# 07_AD9363.net
KiCad netlist of a schematic drawn in Altium Designer
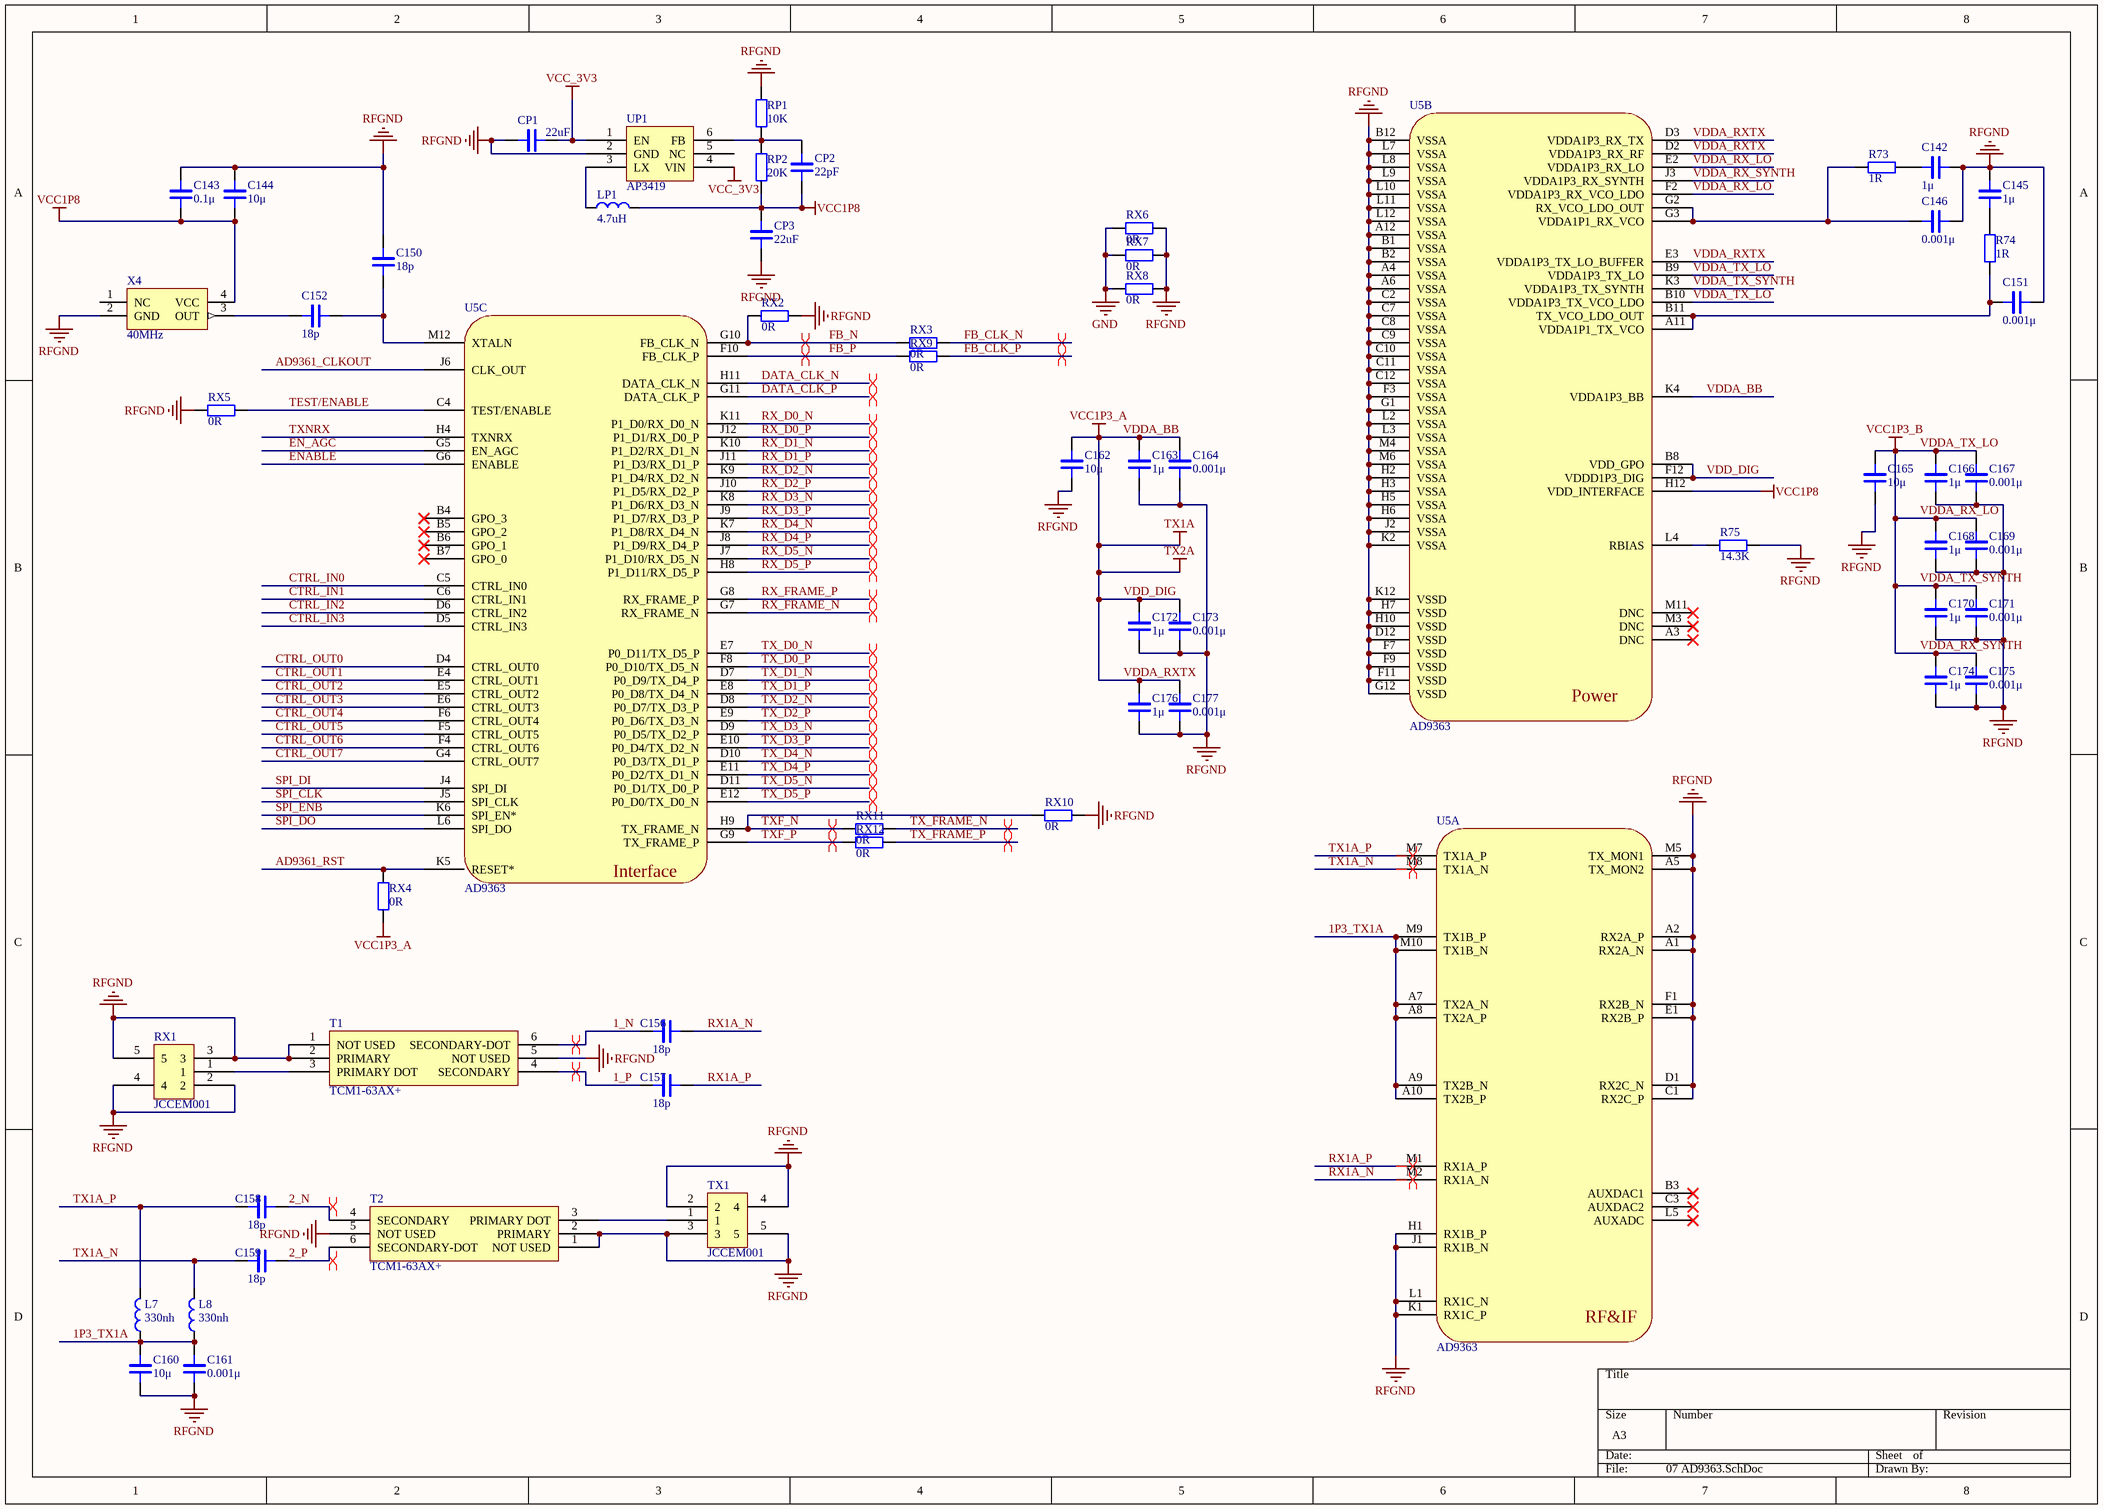
[diagram p0: 07 AD9363.SchDoc]

(export (version "E")
  (design (tool "Eeschema 10.0.6"))
  (components
    (comp (ref "C142")
      (value "1μ")
      (footprint "LC-0402_C")
      (description "Capacitor")
      (libsource (lib "DDR3_xc7z010-clg400") (part "CAP_2"))
    )
    (comp (ref "C143")
      (value "0.1μ")
      (footprint "LC-0402_C")
      (description "Capacitor")
      (libsource (lib "DDR3_xc7z010-clg400") (part "CAP_2"))
    )
    (comp (ref "C144")
      (value "10μ")
      (footprint "LC-0402_C")
      (description "Capacitor")
      (libsource (lib "DDR3_xc7z010-clg400") (part "CAP_2"))
    )
    (comp (ref "C145")
      (value "1μ")
      (footprint "LC-0402_C")
      (description "Capacitor")
      (libsource (lib "DDR3_xc7z010-clg400") (part "CAP_1"))
    )
    (comp (ref "C146")
      (value "0.001μ")
      (footprint "LC-0402_C")
      (description "Capacitor")
      (libsource (lib "DDR3_xc7z010-clg400") (part "CAP_1"))
    )
    (comp (ref "C150")
      (value "18p")
      (footprint "LC-0402_C")
      (description "Capacitor")
      (libsource (lib "DDR3_xc7z010-clg400") (part "CAP_1"))
    )
    (comp (ref "C151")
      (value "0.001μ")
      (footprint "LC-0402_C")
      (description "Capacitor")
      (libsource (lib "DDR3_xc7z010-clg400") (part "CAP_1"))
    )
    (comp (ref "C152")
      (value "18p")
      (footprint "LC-0402_C")
      (description "Capacitor")
      (libsource (lib "DDR3_xc7z010-clg400") (part "CAP_1"))
    )
    (comp (ref "C156")
      (value "18p")
      (footprint "LC-0402_C")
      (description "Capacitor")
      (libsource (lib "DDR3_xc7z010-clg400") (part "CAP_1"))
    )
    (comp (ref "C157")
      (value "18p")
      (footprint "LC-0402_C")
      (description "Capacitor")
      (libsource (lib "DDR3_xc7z010-clg400") (part "CAP_1"))
    )
    (comp (ref "C158")
      (value "18p")
      (footprint "LC-0402_C")
      (description "Capacitor")
      (libsource (lib "DDR3_xc7z010-clg400") (part "CAP_1"))
    )
    (comp (ref "C159")
      (value "18p")
      (footprint "LC-0402_C")
      (description "Capacitor")
      (libsource (lib "DDR3_xc7z010-clg400") (part "CAP_1"))
    )
    (comp (ref "C160")
      (value "10μ")
      (footprint "LC-0402_C")
      (description "Capacitor")
      (libsource (lib "DDR3_xc7z010-clg400") (part "CAP_2"))
    )
    (comp (ref "C161")
      (value "0.001μ")
      (footprint "LC-0402_C")
      (description "Capacitor")
      (libsource (lib "DDR3_xc7z010-clg400") (part "CAP_2"))
    )
    (comp (ref "C162")
      (value "10μ")
      (footprint "LC-0402_C")
      (description "Capacitor")
      (libsource (lib "DDR3_xc7z010-clg400") (part "CAP_1"))
    )
    (comp (ref "C163")
      (value "1μ")
      (footprint "LC-0402_C")
      (description "Capacitor")
      (libsource (lib "DDR3_xc7z010-clg400") (part "CAP_1"))
    )
    (comp (ref "C164")
      (value "0.001μ")
      (footprint "LC-0402_C")
      (description "Capacitor")
      (libsource (lib "DDR3_xc7z010-clg400") (part "CAP_1"))
    )
    (comp (ref "C165")
      (value "10μ")
      (footprint "LC-0402_C")
      (description "Capacitor")
      (libsource (lib "DDR3_xc7z010-clg400") (part "CAP_1"))
    )
    (comp (ref "C166")
      (value "1μ")
      (footprint "LC-0402_C")
      (description "Capacitor")
      (libsource (lib "DDR3_xc7z010-clg400") (part "CAP_1"))
    )
    (comp (ref "C167")
      (value "0.001μ")
      (footprint "LC-0402_C")
      (description "Capacitor")
      (libsource (lib "DDR3_xc7z010-clg400") (part "CAP_1"))
    )
    (comp (ref "C168")
      (value "1μ")
      (footprint "LC-0402_C")
      (description "Capacitor")
      (libsource (lib "DDR3_xc7z010-clg400") (part "CAP_1"))
    )
    (comp (ref "C169")
      (value "0.001μ")
      (footprint "LC-0402_C")
      (description "Capacitor")
      (libsource (lib "DDR3_xc7z010-clg400") (part "CAP_1"))
    )
    (comp (ref "C170")
      (value "1μ")
      (footprint "LC-0402_C")
      (description "Capacitor")
      (libsource (lib "DDR3_xc7z010-clg400") (part "CAP_1"))
    )
    (comp (ref "C171")
      (value "0.001μ")
      (footprint "LC-0402_C")
      (description "Capacitor")
      (libsource (lib "DDR3_xc7z010-clg400") (part "CAP_1"))
    )
    (comp (ref "C172")
      (value "1μ")
      (footprint "LC-0402_C")
      (description "Capacitor")
      (libsource (lib "DDR3_xc7z010-clg400") (part "CAP_1"))
    )
    (comp (ref "C173")
      (value "0.001μ")
      (footprint "LC-0402_C")
      (description "Capacitor")
      (libsource (lib "DDR3_xc7z010-clg400") (part "CAP_1"))
    )
    (comp (ref "C174")
      (value "1μ")
      (footprint "LC-0402_C")
      (description "Capacitor")
      (libsource (lib "DDR3_xc7z010-clg400") (part "CAP_1"))
    )
    (comp (ref "C175")
      (value "0.001μ")
      (footprint "LC-0402_C")
      (description "Capacitor")
      (libsource (lib "DDR3_xc7z010-clg400") (part "CAP_1"))
    )
    (comp (ref "C176")
      (value "1μ")
      (footprint "LC-0402_C")
      (description "Capacitor")
      (libsource (lib "DDR3_xc7z010-clg400") (part "CAP_1"))
    )
    (comp (ref "C177")
      (value "0.001μ")
      (footprint "LC-0402_C")
      (description "Capacitor")
      (libsource (lib "DDR3_xc7z010-clg400") (part "CAP_1"))
    )
    (comp (ref "CP1")
      (value "22uF")
      (footprint "LC-0805_C")
      (description "Capacitor")
      (libsource (lib "DDR3_xc7z010-clg400") (part "CAP_1"))
    )
    (comp (ref "CP2")
      (value "22pF")
      (footprint "LC-0402_C")
      (description "Capacitor")
      (libsource (lib "DDR3_xc7z010-clg400") (part "CAP_2"))
    )
    (comp (ref "CP3")
      (value "22uF")
      (footprint "LC-0805_C")
      (description "Capacitor")
      (libsource (lib "DDR3_xc7z010-clg400") (part "CAP_1"))
    )
    (comp (ref "L7")
      (value "330nh")
      (footprint "LC-0603_L")
      (description "Inductance")
      (libsource (lib "DDR3_xc7z010-clg400") (part "INDUCTANCE"))
    )
    (comp (ref "L8")
      (value "330nh")
      (footprint "LC-0603_L")
      (description "Inductance")
      (libsource (lib "DDR3_xc7z010-clg400") (part "INDUCTANCE"))
    )
    (comp (ref "LP1")
      (value "4.7uH")
      (footprint "L1008")
      (description "Inductance")
      (libsource (lib "DDR3_xc7z010-clg400") (part "INDUCTANCE"))
    )
    (comp (ref "R73")
      (value "1R")
      (footprint "LC-0402_R")
      (description "Resistor")
      (libsource (lib "") (part "RES_1_1"))
    )
    (comp (ref "R74")
      (value "1R")
      (footprint "LC-0402_R")
      (description "Resistor")
      (libsource (lib "") (part "RES_1_2"))
    )
    (comp (ref "R75")
      (value "14.3K")
      (footprint "LC-0402_R")
      (description "Resistor")
      (libsource (lib "") (part "RES_1_1"))
    )
    (comp (ref "RP1")
      (value "10K")
      (footprint "LC-0402_R")
      (description "Resistor")
      (libsource (lib "") (part "RES_1_3"))
    )
    (comp (ref "RP2")
      (value "20K")
      (footprint "LC-0402_R")
      (description "Resistor")
      (libsource (lib "") (part "RES_1_3"))
    )
    (comp (ref "RX1")
      (value "JCCEM001")
      (footprint "CNSMARAL687W375H171")
      (libsource (lib "Schlib1") (part "JCCEM001"))
    )
    (comp (ref "RX2")
      (value "0R")
      (footprint "LC-0402_R")
      (description "Resistor")
      (libsource (lib "DDR3_xc7z010-clg400") (part "RES_1"))
    )
    (comp (ref "RX3")
      (value "0R")
      (footprint "LC-0402_R")
      (description "Resistor")
      (libsource (lib "DDR3_xc7z010-clg400") (part "RES_1"))
    )
    (comp (ref "RX4")
      (value "0R")
      (footprint "LC-0402_R")
      (description "Resistor")
      (libsource (lib "") (part "RES_1_2"))
    )
    (comp (ref "RX5")
      (value "0R")
      (footprint "LC-0402_R")
      (description "Resistor")
      (libsource (lib "") (part "RES_1_1"))
    )
    (comp (ref "RX6")
      (value "0R")
      (footprint "LC-0603_L")
      (description "Resistor")
      (libsource (lib "DDR3_xc7z010-clg400") (part "RES_1"))
    )
    (comp (ref "RX7")
      (value "0R")
      (footprint "LC-0603_L")
      (description "Resistor")
      (libsource (lib "DDR3_xc7z010-clg400") (part "RES_1"))
    )
    (comp (ref "RX8")
      (value "0R")
      (footprint "LC-0603_L")
      (description "Resistor")
      (libsource (lib "DDR3_xc7z010-clg400") (part "RES_1"))
    )
    (comp (ref "RX9")
      (value "0R")
      (footprint "LC-0402_R")
      (description "Resistor")
      (libsource (lib "DDR3_xc7z010-clg400") (part "RES_1"))
    )
    (comp (ref "RX10")
      (value "0R")
      (footprint "LC-0402_R")
      (description "Resistor")
      (libsource (lib "DDR3_xc7z010-clg400") (part "RES_1"))
    )
    (comp (ref "RX11")
      (value "0R")
      (footprint "LC-0402_R")
      (description "Resistor")
      (libsource (lib "DDR3_xc7z010-clg400") (part "RES_1"))
    )
    (comp (ref "RX12")
      (value "0R")
      (footprint "LC-0402_R")
      (description "Resistor")
      (libsource (lib "DDR3_xc7z010-clg400") (part "RES_1"))
    )
    (comp (ref "T1")
      (value "TCM1-63AX+")
      (footprint "TSML150W160H160")
      (libsource (lib "Schlib1") (part "TCM1-63AX+"))
    )
    (comp (ref "T2")
      (value "TCM1-63AX+")
      (footprint "TSML150W160H160")
      (libsource (lib "") (part "TCM1-63AX+_1"))
    )
    (comp (ref "TX1")
      (value "JCCEM001")
      (footprint "CNSMARAL687W375H171")
      (libsource (lib "") (part "JCCEM001_1"))
    )
    (comp (ref "U5") (value "AD9363") (footprint "AD936X") (libsource (lib "Schlib1") (part "AD9363")))
    (comp (ref "UP1") (value "AP3419") (footprint "AP3419") (libsource (lib "Schlib1") (part "AP3419")))
    (comp (ref "X4")
      (value "40MHz")
      (footprint "OSC-SMD_4P-L3.2-W2.5-BL")
      (description "Oscillator")
      (libsource (lib "DDR3_xc7z010-clg400") (part "XTAL-4"))
    )
  )
  (nets
    (net (code "1") (name "/1P3_TX1A") (class "Default")
      (node (ref "C160") (pin "1") (pinfunction "1_1") (pintype "passive"))
      (node (ref "C161") (pin "2") (pinfunction "2_2") (pintype "passive"))
      (node (ref "L7") (pin "1") (pinfunction "1_1") (pintype "passive"))
      (node (ref "L8") (pin "1") (pinfunction "1_1") (pintype "passive"))
      (node (ref "U5") (pin "A10") (pinfunction "TX2B_P_A10") (pintype "passive"))
      (node (ref "U5") (pin "A7") (pinfunction "TX2A_N_A7") (pintype "passive"))
      (node (ref "U5") (pin "A8") (pinfunction "TX2A_P_A8") (pintype "passive"))
      (node (ref "U5") (pin "A9") (pinfunction "TX2B_N_A9") (pintype "passive"))
      (node (ref "U5") (pin "M10") (pinfunction "TX1B_N_M10") (pintype "passive"))
      (node (ref "U5") (pin "M9") (pinfunction "TX1B_P_M9") (pintype "passive"))
    )
    (net (code "2") (name "/1_N") (class "Default")
      (node (ref "C156") (pin "1") (pinfunction "1_1") (pintype "passive"))
      (node (ref "T1") (pin "6") (pinfunction "SECONDARY-DOT_6") (pintype "passive"))
    )
    (net (code "3") (name "/1_P") (class "Default")
      (node (ref "C157") (pin "1") (pinfunction "1_1") (pintype "passive"))
      (node (ref "T1") (pin "4") (pinfunction "SECONDARY_4") (pintype "passive"))
    )
    (net (code "4") (name "/2_N") (class "Default")
      (node (ref "C158") (pin "2") (pinfunction "2_2") (pintype "passive"))
      (node (ref "T2") (pin "4") (pinfunction "SECONDARY_4") (pintype "passive"))
    )
    (net (code "5") (name "/2_P") (class "Default")
      (node (ref "C159") (pin "2") (pinfunction "2_2") (pintype "passive"))
      (node (ref "T2") (pin "6") (pinfunction "SECONDARY-DOT_6") (pintype "passive"))
    )
    (net (code "6") (name "/AD9361_CLKOUT") (class "Default")
      (node (ref "U5") (pin "J6") (pinfunction "CLK_OUT_J6") (pintype "passive"))
    )
    (net (code "7") (name "/AD9361_RST") (class "Default")
      (node (ref "RX4") (pin "1") (pinfunction "1_1") (pintype "passive"))
      (node (ref "U5") (pin "K5") (pinfunction "RESET*_K5") (pintype "passive"))
    )
    (net (code "8") (name "/CTRL_IN0") (class "Default")
      (node (ref "U5") (pin "C5") (pinfunction "CTRL_IN0_C5") (pintype "passive"))
    )
    (net (code "9") (name "/CTRL_IN1") (class "Default")
      (node (ref "U5") (pin "C6") (pinfunction "CTRL_IN1_C6") (pintype "passive"))
    )
    (net (code "10") (name "/CTRL_IN2") (class "Default")
      (node (ref "U5") (pin "D6") (pinfunction "CTRL_IN2_D6") (pintype "passive"))
    )
    (net (code "11") (name "/CTRL_IN3") (class "Default")
      (node (ref "U5") (pin "D5") (pinfunction "CTRL_IN3_D5") (pintype "passive"))
    )
    (net (code "12") (name "/CTRL_OUT0") (class "Default")
      (node (ref "U5") (pin "D4") (pinfunction "CTRL_OUT0_D4") (pintype "passive"))
    )
    (net (code "13") (name "/CTRL_OUT1") (class "Default")
      (node (ref "U5") (pin "E4") (pinfunction "CTRL_OUT1_E4") (pintype "passive"))
    )
    (net (code "14") (name "/CTRL_OUT2") (class "Default")
      (node (ref "U5") (pin "E5") (pinfunction "CTRL_OUT2_E5") (pintype "passive"))
    )
    (net (code "15") (name "/CTRL_OUT3") (class "Default")
      (node (ref "U5") (pin "E6") (pinfunction "CTRL_OUT3_E6") (pintype "passive"))
    )
    (net (code "16") (name "/CTRL_OUT4") (class "Default")
      (node (ref "U5") (pin "F6") (pinfunction "CTRL_OUT4_F6") (pintype "passive"))
    )
    (net (code "17") (name "/CTRL_OUT5") (class "Default")
      (node (ref "U5") (pin "F5") (pinfunction "CTRL_OUT5_F5") (pintype "passive"))
    )
    (net (code "18") (name "/CTRL_OUT6") (class "Default")
      (node (ref "U5") (pin "F4") (pinfunction "CTRL_OUT6_F4") (pintype "passive"))
    )
    (net (code "19") (name "/CTRL_OUT7") (class "Default")
      (node (ref "U5") (pin "G4") (pinfunction "CTRL_OUT7_G4") (pintype "passive"))
    )
    (net (code "20") (name "/DATA_CLK_N") (class "Default")
      (node (ref "U5") (pin "H11") (pinfunction "DATA_CLK_N_H11") (pintype "passive"))
    )
    (net (code "21") (name "/DATA_CLK_P") (class "Default")
      (node (ref "U5") (pin "G11") (pinfunction "DATA_CLK_P_G11") (pintype "passive"))
    )
    (net (code "22") (name "/ENABLE") (class "Default")
      (node (ref "U5") (pin "G6") (pinfunction "ENABLE_G6") (pintype "passive"))
    )
    (net (code "23") (name "/EN_AGC") (class "Default")
      (node (ref "U5") (pin "G5") (pinfunction "EN_AGC_G5") (pintype "passive"))
    )
    (net (code "24") (name "/FB_CLK_N") (class "Default")
      (node (ref "RX3") (pin "1") (pinfunction "1_1") (pintype "passive"))
    )
    (net (code "25") (name "/FB_CLK_P") (class "Default")
      (node (ref "RX9") (pin "1") (pinfunction "1_1") (pintype "passive"))
    )
    (net (code "26") (name "/FB_N") (class "Default")
      (node (ref "RX2") (pin "2") (pinfunction "2_2") (pintype "passive"))
      (node (ref "RX3") (pin "2") (pinfunction "2_2") (pintype "passive"))
      (node (ref "U5") (pin "G10") (pinfunction "FB_CLK_N_G10") (pintype "passive"))
    )
    (net (code "27") (name "/FB_P") (class "Default")
      (node (ref "RX9") (pin "2") (pinfunction "2_2") (pintype "passive"))
      (node (ref "U5") (pin "F10") (pinfunction "FB_CLK_P_F10") (pintype "passive"))
    )
    (net (code "28") (name "/RX1A_N") (class "Default")
      (node (ref "C156") (pin "2") (pinfunction "2_2") (pintype "passive"))
      (node (ref "U5") (pin "M2") (pinfunction "RX1A_N_M2") (pintype "passive"))
    )
    (net (code "29") (name "/RX1A_P") (class "Default")
      (node (ref "C157") (pin "2") (pinfunction "2_2") (pintype "passive"))
      (node (ref "U5") (pin "M1") (pinfunction "RX1A_P_M1") (pintype "passive"))
    )
    (net (code "30") (name "/RX_D0_N") (class "Default")
      (node (ref "U5") (pin "K11") (pinfunction "P1_D0/RX_D0_N_K11") (pintype "passive"))
    )
    (net (code "31") (name "/RX_D0_P") (class "Default")
      (node (ref "U5") (pin "J12") (pinfunction "P1_D1/RX_D0_P_J12") (pintype "passive"))
    )
    (net (code "32") (name "/RX_D1_N") (class "Default")
      (node (ref "U5") (pin "K10") (pinfunction "P1_D2/RX_D1_N_K10") (pintype "passive"))
    )
    (net (code "33") (name "/RX_D1_P") (class "Default")
      (node (ref "U5") (pin "J11") (pinfunction "P1_D3/RX_D1_P_J11") (pintype "passive"))
    )
    (net (code "34") (name "/RX_D2_N") (class "Default")
      (node (ref "U5") (pin "K9") (pinfunction "P1_D4/RX_D2_N_K9") (pintype "passive"))
    )
    (net (code "35") (name "/RX_D2_P") (class "Default")
      (node (ref "U5") (pin "J10") (pinfunction "P1_D5/RX_D2_P_J10") (pintype "passive"))
    )
    (net (code "36") (name "/RX_D3_N") (class "Default")
      (node (ref "U5") (pin "K8") (pinfunction "P1_D6/RX_D3_N_K8") (pintype "passive"))
    )
    (net (code "37") (name "/RX_D3_P") (class "Default")
      (node (ref "U5") (pin "J9") (pinfunction "P1_D7/RX_D3_P_J9") (pintype "passive"))
    )
    (net (code "38") (name "/RX_D4_N") (class "Default")
      (node (ref "U5") (pin "K7") (pinfunction "P1_D8/RX_D4_N_K7") (pintype "passive"))
    )
    (net (code "39") (name "/RX_D4_P") (class "Default")
      (node (ref "U5") (pin "J8") (pinfunction "P1_D9/RX_D4_P_J8") (pintype "passive"))
    )
    (net (code "40") (name "/RX_D5_N") (class "Default")
      (node (ref "U5") (pin "J7") (pinfunction "P1_D10/RX_D5_N_J7") (pintype "passive"))
    )
    (net (code "41") (name "/RX_D5_P") (class "Default")
      (node (ref "U5") (pin "H8") (pinfunction "P1_D11/RX_D5_P_H8") (pintype "passive"))
    )
    (net (code "42") (name "/RX_FRAME_N") (class "Default")
      (node (ref "U5") (pin "G7") (pinfunction "RX_FRAME_N_G7") (pintype "passive"))
    )
    (net (code "43") (name "/RX_FRAME_P") (class "Default")
      (node (ref "U5") (pin "G8") (pinfunction "RX_FRAME_P_G8") (pintype "passive"))
    )
    (net (code "44") (name "/SPI_CLK") (class "Default")
      (node (ref "U5") (pin "J5") (pinfunction "SPI_CLK_J5") (pintype "passive"))
    )
    (net (code "45") (name "/SPI_DI") (class "Default")
      (node (ref "U5") (pin "J4") (pinfunction "SPI_DI_J4") (pintype "passive"))
    )
    (net (code "46") (name "/SPI_DO") (class "Default")
      (node (ref "U5") (pin "L6") (pinfunction "SPI_DO_L6") (pintype "passive"))
    )
    (net (code "47") (name "/SPI_ENB") (class "Default")
      (node (ref "U5") (pin "K6") (pinfunction "SPI_EN*_K6") (pintype "passive"))
    )
    (net (code "48") (name "/TEST{slash}ENABLE") (class "Default")
      (node (ref "RX5") (pin "2") (pinfunction "2_2") (pintype "passive"))
      (node (ref "U5") (pin "C4") (pinfunction "TEST/ENABLE_C4") (pintype "passive"))
    )
    (net (code "49") (name "/TX1A_N") (class "Default")
      (node (ref "C159") (pin "1") (pinfunction "1_1") (pintype "passive"))
      (node (ref "L8") (pin "2") (pinfunction "2_2") (pintype "passive"))
      (node (ref "U5") (pin "M8") (pinfunction "TX1A_N_M8") (pintype "passive"))
    )
    (net (code "50") (name "/TX1A_P") (class "Default")
      (node (ref "C158") (pin "1") (pinfunction "1_1") (pintype "passive"))
      (node (ref "L7") (pin "2") (pinfunction "2_2") (pintype "passive"))
      (node (ref "U5") (pin "M7") (pinfunction "TX1A_P_M7") (pintype "passive"))
    )
    (net (code "51") (name "/TXF_N") (class "Default")
      (node (ref "RX10") (pin "2") (pinfunction "2_2") (pintype "passive"))
      (node (ref "RX11") (pin "2") (pinfunction "2_2") (pintype "passive"))
      (node (ref "U5") (pin "H9") (pinfunction "TX_FRAME_N_H9") (pintype "passive"))
    )
    (net (code "52") (name "/TXF_P") (class "Default")
      (node (ref "RX12") (pin "2") (pinfunction "2_2") (pintype "passive"))
      (node (ref "U5") (pin "G9") (pinfunction "TX_FRAME_P_G9") (pintype "passive"))
    )
    (net (code "53") (name "/TXNRX") (class "Default")
      (node (ref "U5") (pin "H4") (pinfunction "TXNRX_H4") (pintype "passive"))
    )
    (net (code "54") (name "/TX_D0_N") (class "Default")
      (node (ref "U5") (pin "E7") (pinfunction "P0_D11/TX_D5_P_E7") (pintype "passive"))
    )
    (net (code "55") (name "/TX_D0_P") (class "Default")
      (node (ref "U5") (pin "F8") (pinfunction "P0_D10/TX_D5_N_F8") (pintype "passive"))
    )
    (net (code "56") (name "/TX_D1_N") (class "Default")
      (node (ref "U5") (pin "D7") (pinfunction "P0_D9/TX_D4_P_D7") (pintype "passive"))
    )
    (net (code "57") (name "/TX_D1_P") (class "Default")
      (node (ref "U5") (pin "E8") (pinfunction "P0_D8/TX_D4_N_E8") (pintype "passive"))
    )
    (net (code "58") (name "/TX_D2_N") (class "Default")
      (node (ref "U5") (pin "D8") (pinfunction "P0_D7/TX_D3_P_D8") (pintype "passive"))
    )
    (net (code "59") (name "/TX_D2_P") (class "Default")
      (node (ref "U5") (pin "E9") (pinfunction "P0_D6/TX_D3_N_E9") (pintype "passive"))
    )
    (net (code "60") (name "/TX_D3_N") (class "Default")
      (node (ref "U5") (pin "D9") (pinfunction "P0_D5/TX_D2_P_D9") (pintype "passive"))
    )
    (net (code "61") (name "/TX_D3_P") (class "Default")
      (node (ref "U5") (pin "E10") (pinfunction "P0_D4/TX_D2_N_E10") (pintype "passive"))
    )
    (net (code "62") (name "/TX_D4_N") (class "Default")
      (node (ref "U5") (pin "D10") (pinfunction "P0_D3/TX_D1_P_D10") (pintype "passive"))
    )
    (net (code "63") (name "/TX_D4_P") (class "Default")
      (node (ref "U5") (pin "E11") (pinfunction "P0_D2/TX_D1_N_E11") (pintype "passive"))
    )
    (net (code "64") (name "/TX_D5_N") (class "Default")
      (node (ref "U5") (pin "D11") (pinfunction "P0_D1/TX_D0_P_D11") (pintype "passive"))
    )
    (net (code "65") (name "/TX_D5_P") (class "Default")
      (node (ref "U5") (pin "E12") (pinfunction "P0_D0/TX_D0_N_E12") (pintype "passive"))
    )
    (net (code "66") (name "/TX_FRAME_N") (class "Default")
      (node (ref "RX11") (pin "1") (pinfunction "1_1") (pintype "passive"))
    )
    (net (code "67") (name "/TX_FRAME_P") (class "Default")
      (node (ref "RX12") (pin "1") (pinfunction "1_1") (pintype "passive"))
    )
    (net (code "68") (name "GND") (class "Default")
      (node (ref "RX6") (pin "2") (pinfunction "2_2") (pintype "passive"))
      (node (ref "RX7") (pin "2") (pinfunction "2_2") (pintype "passive"))
      (node (ref "RX8") (pin "2") (pinfunction "2_2") (pintype "passive"))
    )
    (net (code "69") (name "Net-(C142-Pad1)") (class "Default")
      (node (ref "C142") (pin "1") (pinfunction "1_1") (pintype "passive"))
      (node (ref "R73") (pin "2") (pinfunction "2_2") (pintype "passive"))
    )
    (net (code "70") (name "Net-(C145-Pad2)") (class "Default")
      (node (ref "C145") (pin "2") (pinfunction "2_2") (pintype "passive"))
      (node (ref "R74") (pin "1") (pinfunction "1_1") (pintype "passive"))
    )
    (net (code "71") (name "Net-(T1-PRIMARY_DOT)") (class "Default")
      (node (ref "RX1") (pin "1") (pinfunction "1_1") (pintype "passive"))
      (node (ref "T1") (pin "3") (pinfunction "PRIMARY_DOT_3") (pintype "passive"))
    )
    (net (code "72") (name "Net-(T2-PRIMARY_DOT)") (class "Default")
      (node (ref "T2") (pin "3") (pinfunction "PRIMARY_DOT_3") (pintype "passive"))
      (node (ref "TX1") (pin "1") (pinfunction "1_1") (pintype "passive"))
    )
    (net (code "73") (name "Net-(U5B-RBIAS)") (class "Default")
      (node (ref "R75") (pin "1") (pinfunction "1_1") (pintype "passive"))
      (node (ref "U5") (pin "L4") (pinfunction "RBIAS_L4") (pintype "passive"))
    )
    (net (code "74") (name "Net-(U5B-RX_VCO_LDO_OUT)") (class "Default")
      (node (ref "C146") (pin "2") (pinfunction "2_2") (pintype "passive"))
      (node (ref "R73") (pin "1") (pinfunction "1_1") (pintype "passive"))
      (node (ref "U5") (pin "G2") (pinfunction "RX_VCO_LDO_OUT_G2") (pintype "passive"))
      (node (ref "U5") (pin "G3") (pinfunction "VDDA1P1_RX_VCO_G3") (pintype "passive"))
    )
    (net (code "75") (name "Net-(U5B-TX_VCO_LDO_OUT)") (class "Default")
      (node (ref "C151") (pin "2") (pinfunction "2_2") (pintype "passive"))
      (node (ref "R74") (pin "2") (pinfunction "2_2") (pintype "passive"))
      (node (ref "U5") (pin "A11") (pinfunction "VDDA1P1_TX_VCO_A11") (pintype "passive"))
      (node (ref "U5") (pin "B11") (pinfunction "TX_VCO_LDO_OUT_B11") (pintype "passive"))
    )
    (net (code "76") (name "Net-(U5C-XTALN)") (class "Default")
      (node (ref "C150") (pin "2") (pinfunction "2_2") (pintype "passive"))
      (node (ref "C152") (pin "1") (pinfunction "1_1") (pintype "passive"))
      (node (ref "U5") (pin "M12") (pinfunction "XTALN_M12") (pintype "passive"))
    )
    (net (code "77") (name "Net-(UP1-FB)") (class "Default")
      (node (ref "CP2") (pin "2") (pinfunction "2_2") (pintype "passive"))
      (node (ref "RP1") (pin "1") (pinfunction "1_1") (pintype "passive"))
      (node (ref "RP2") (pin "2") (pinfunction "2_2") (pintype "passive"))
      (node (ref "UP1") (pin "6") (pinfunction "FB_6") (pintype "passive"))
    )
    (net (code "78") (name "Net-(UP1-LX)") (class "Default")
      (node (ref "LP1") (pin "1") (pinfunction "1_1") (pintype "passive"))
      (node (ref "UP1") (pin "3") (pinfunction "LX_3") (pintype "passive"))
    )
    (net (code "79") (name "Net-(X4-OUT)") (class "Default")
      (node (ref "C152") (pin "2") (pinfunction "2_2") (pintype "passive"))
      (node (ref "X4") (pin "3") (pinfunction "OUT_3") (pintype "output"))
    )
    (net (code "80") (name "RFGND") (class "Default")
      (node (ref "C142") (pin "2") (pinfunction "2_2") (pintype "passive"))
      (node (ref "C143") (pin "1") (pinfunction "1_1") (pintype "passive"))
      (node (ref "C144") (pin "1") (pinfunction "1_1") (pintype "passive"))
      (node (ref "C145") (pin "1") (pinfunction "1_1") (pintype "passive"))
      (node (ref "C146") (pin "1") (pinfunction "1_1") (pintype "passive"))
      (node (ref "C150") (pin "1") (pinfunction "1_1") (pintype "passive"))
      (node (ref "C151") (pin "1") (pinfunction "1_1") (pintype "passive"))
      (node (ref "C160") (pin "2") (pinfunction "2_2") (pintype "passive"))
      (node (ref "C161") (pin "1") (pinfunction "1_1") (pintype "passive"))
      (node (ref "C162") (pin "2") (pinfunction "2_2") (pintype "passive"))
      (node (ref "C163") (pin "2") (pinfunction "2_2") (pintype "passive"))
      (node (ref "C164") (pin "2") (pinfunction "2_2") (pintype "passive"))
      (node (ref "C165") (pin "2") (pinfunction "2_2") (pintype "passive"))
      (node (ref "C166") (pin "2") (pinfunction "2_2") (pintype "passive"))
      (node (ref "C167") (pin "2") (pinfunction "2_2") (pintype "passive"))
      (node (ref "C168") (pin "2") (pinfunction "2_2") (pintype "passive"))
      (node (ref "C169") (pin "2") (pinfunction "2_2") (pintype "passive"))
      (node (ref "C170") (pin "2") (pinfunction "2_2") (pintype "passive"))
      (node (ref "C171") (pin "2") (pinfunction "2_2") (pintype "passive"))
      (node (ref "C172") (pin "2") (pinfunction "2_2") (pintype "passive"))
      (node (ref "C173") (pin "2") (pinfunction "2_2") (pintype "passive"))
      (node (ref "C174") (pin "2") (pinfunction "2_2") (pintype "passive"))
      (node (ref "C175") (pin "2") (pinfunction "2_2") (pintype "passive"))
      (node (ref "C176") (pin "2") (pinfunction "2_2") (pintype "passive"))
      (node (ref "C177") (pin "2") (pinfunction "2_2") (pintype "passive"))
      (node (ref "CP1") (pin "1") (pinfunction "1_1") (pintype "passive"))
      (node (ref "CP3") (pin "1") (pinfunction "1_1") (pintype "passive"))
      (node (ref "R75") (pin "2") (pinfunction "2_2") (pintype "passive"))
      (node (ref "RP1") (pin "2") (pinfunction "2_2") (pintype "passive"))
      (node (ref "RX1") (pin "2") (pinfunction "2_2") (pintype "passive"))
      (node (ref "RX1") (pin "3") (pinfunction "3_3") (pintype "passive"))
      (node (ref "RX1") (pin "4") (pinfunction "4_4") (pintype "passive"))
      (node (ref "RX1") (pin "5") (pinfunction "5_5") (pintype "passive"))
      (node (ref "RX10") (pin "1") (pinfunction "1_1") (pintype "passive"))
      (node (ref "RX2") (pin "1") (pinfunction "1_1") (pintype "passive"))
      (node (ref "RX5") (pin "1") (pinfunction "1_1") (pintype "passive"))
      (node (ref "RX6") (pin "1") (pinfunction "1_1") (pintype "passive"))
      (node (ref "RX7") (pin "1") (pinfunction "1_1") (pintype "passive"))
      (node (ref "RX8") (pin "1") (pinfunction "1_1") (pintype "passive"))
      (node (ref "T1") (pin "1") (pinfunction "NOT_USED_1") (pintype "passive"))
      (node (ref "T1") (pin "2") (pinfunction "PRIMARY_2") (pintype "passive"))
      (node (ref "T1") (pin "5") (pinfunction "NOT_USED_5") (pintype "passive"))
      (node (ref "T2") (pin "1") (pinfunction "NOT_USED_1") (pintype "passive"))
      (node (ref "T2") (pin "2") (pinfunction "PRIMARY_2") (pintype "passive"))
      (node (ref "T2") (pin "5") (pinfunction "NOT_USED_5") (pintype "passive"))
      (node (ref "TX1") (pin "2") (pinfunction "2_2") (pintype "passive"))
      (node (ref "TX1") (pin "3") (pinfunction "3_3") (pintype "passive"))
      (node (ref "TX1") (pin "4") (pinfunction "4_4") (pintype "passive"))
      (node (ref "TX1") (pin "5") (pinfunction "5_5") (pintype "passive"))
      (node (ref "U5") (pin "A1") (pinfunction "RX2A_N_A1") (pintype "passive"))
      (node (ref "U5") (pin "A12") (pinfunction "VSSA_A12") (pintype "passive"))
      (node (ref "U5") (pin "A2") (pinfunction "RX2A_P_A2") (pintype "passive"))
      (node (ref "U5") (pin "A4") (pinfunction "VSSA_A4") (pintype "passive"))
      (node (ref "U5") (pin "A5") (pinfunction "TX_MON2_A5") (pintype "passive"))
      (node (ref "U5") (pin "A6") (pinfunction "VSSA_A6") (pintype "passive"))
      (node (ref "U5") (pin "B1") (pinfunction "VSSA_B1") (pintype "passive"))
      (node (ref "U5") (pin "B12") (pinfunction "VSSA_B12") (pintype "passive"))
      (node (ref "U5") (pin "B2") (pinfunction "VSSA_B2") (pintype "passive"))
      (node (ref "U5") (pin "C1") (pinfunction "RX2C_P_C1") (pintype "passive"))
      (node (ref "U5") (pin "C10") (pinfunction "VSSA_C10") (pintype "passive"))
      (node (ref "U5") (pin "C11") (pinfunction "VSSA_C11") (pintype "passive"))
      (node (ref "U5") (pin "C12") (pinfunction "VSSA_C12") (pintype "passive"))
      (node (ref "U5") (pin "C2") (pinfunction "VSSA_C2") (pintype "passive"))
      (node (ref "U5") (pin "C7") (pinfunction "VSSA_C7") (pintype "passive"))
      (node (ref "U5") (pin "C8") (pinfunction "VSSA_C8") (pintype "passive"))
      (node (ref "U5") (pin "C9") (pinfunction "VSSA_C9") (pintype "passive"))
      (node (ref "U5") (pin "D1") (pinfunction "RX2C_N_D1") (pintype "passive"))
      (node (ref "U5") (pin "D12") (pinfunction "VSSD_D12") (pintype "passive"))
      (node (ref "U5") (pin "E1") (pinfunction "RX2B_P_E1") (pintype "passive"))
      (node (ref "U5") (pin "F1") (pinfunction "RX2B_N_F1") (pintype "passive"))
      (node (ref "U5") (pin "F11") (pinfunction "VSSD_F11") (pintype "passive"))
      (node (ref "U5") (pin "F3") (pinfunction "VSSA_F3") (pintype "passive"))
      (node (ref "U5") (pin "F7") (pinfunction "VSSD_F7") (pintype "passive"))
      (node (ref "U5") (pin "F9") (pinfunction "VSSD_F9") (pintype "passive"))
      (node (ref "U5") (pin "G1") (pinfunction "VSSA_G1") (pintype "passive"))
      (node (ref "U5") (pin "G12") (pinfunction "VSSD_G12") (pintype "passive"))
      (node (ref "U5") (pin "H1") (pinfunction "RX1B_P_H1") (pintype "passive"))
      (node (ref "U5") (pin "H10") (pinfunction "VSSD_H10") (pintype "passive"))
      (node (ref "U5") (pin "H2") (pinfunction "VSSA_H2") (pintype "passive"))
      (node (ref "U5") (pin "H3") (pinfunction "VSSA_H3") (pintype "passive"))
      (node (ref "U5") (pin "H5") (pinfunction "VSSA_H5") (pintype "passive"))
      (node (ref "U5") (pin "H6") (pinfunction "VSSA_H6") (pintype "passive"))
      (node (ref "U5") (pin "H7") (pinfunction "VSSD_H7") (pintype "passive"))
      (node (ref "U5") (pin "J1") (pinfunction "RX1B_N_J1") (pintype "passive"))
      (node (ref "U5") (pin "J2") (pinfunction "VSSA_J2") (pintype "passive"))
      (node (ref "U5") (pin "K1") (pinfunction "RX1C_P_K1") (pintype "passive"))
      (node (ref "U5") (pin "K12") (pinfunction "VSSD_K12") (pintype "passive"))
      (node (ref "U5") (pin "K2") (pinfunction "VSSA_K2") (pintype "passive"))
      (node (ref "U5") (pin "L1") (pinfunction "RX1C_N_L1") (pintype "passive"))
      (node (ref "U5") (pin "L10") (pinfunction "VSSA_L10") (pintype "passive"))
      (node (ref "U5") (pin "L11") (pinfunction "VSSA_L11") (pintype "passive"))
      (node (ref "U5") (pin "L12") (pinfunction "VSSA_L12") (pintype "passive"))
      (node (ref "U5") (pin "L2") (pinfunction "VSSA_L2") (pintype "passive"))
      (node (ref "U5") (pin "L3") (pinfunction "VSSA_L3") (pintype "passive"))
      (node (ref "U5") (pin "L7") (pinfunction "VSSA_L7") (pintype "passive"))
      (node (ref "U5") (pin "L8") (pinfunction "VSSA_L8") (pintype "passive"))
      (node (ref "U5") (pin "L9") (pinfunction "VSSA_L9") (pintype "passive"))
      (node (ref "U5") (pin "M4") (pinfunction "VSSA_M4") (pintype "passive"))
      (node (ref "U5") (pin "M5") (pinfunction "TX_MON1_M5") (pintype "passive"))
      (node (ref "U5") (pin "M6") (pinfunction "VSSA_M6") (pintype "passive"))
      (node (ref "UP1") (pin "2") (pinfunction "GND_2") (pintype "passive"))
      (node (ref "X4") (pin "2") (pinfunction "GND_2") (pintype "power_in"))
    )
    (net (code "81") (name "TX1A") (class "Default")
      (node (ref "C162") (pin "1") (pinfunction "1_1") (pintype "passive"))
      (node (ref "C163") (pin "1") (pinfunction "1_1") (pintype "passive"))
      (node (ref "C164") (pin "1") (pinfunction "1_1") (pintype "passive"))
      (node (ref "C172") (pin "1") (pinfunction "1_1") (pintype "passive"))
      (node (ref "C173") (pin "1") (pinfunction "1_1") (pintype "passive"))
      (node (ref "C176") (pin "1") (pinfunction "1_1") (pintype "passive"))
      (node (ref "C177") (pin "1") (pinfunction "1_1") (pintype "passive"))
      (node (ref "RX4") (pin "2") (pinfunction "2_2") (pintype "passive"))
      (node (ref "U5") (pin "B8") (pinfunction "VDD_GPO_B8") (pintype "passive"))
      (node (ref "U5") (pin "D2") (pinfunction "VDDA1P3_RX_RF_D2") (pintype "passive"))
      (node (ref "U5") (pin "D3") (pinfunction "VDDA1P3_RX_TX_D3") (pintype "passive"))
      (node (ref "U5") (pin "E3") (pinfunction "VDDA1P3_TX_LO_BUFFER_E3") (pintype "passive"))
      (node (ref "U5") (pin "F12") (pinfunction "VDDD1P3_DIG_F12") (pintype "passive"))
      (node (ref "U5") (pin "K4") (pinfunction "VDDA1P3_BB_K4") (pintype "passive"))
    )
    (net (code "82") (name "VCC1P3_B") (class "Default")
      (node (ref "C165") (pin "1") (pinfunction "1_1") (pintype "passive"))
      (node (ref "C166") (pin "1") (pinfunction "1_1") (pintype "passive"))
      (node (ref "C167") (pin "1") (pinfunction "1_1") (pintype "passive"))
      (node (ref "C168") (pin "1") (pinfunction "1_1") (pintype "passive"))
      (node (ref "C169") (pin "1") (pinfunction "1_1") (pintype "passive"))
      (node (ref "C170") (pin "1") (pinfunction "1_1") (pintype "passive"))
      (node (ref "C171") (pin "1") (pinfunction "1_1") (pintype "passive"))
      (node (ref "C174") (pin "1") (pinfunction "1_1") (pintype "passive"))
      (node (ref "C175") (pin "1") (pinfunction "1_1") (pintype "passive"))
      (node (ref "U5") (pin "B10") (pinfunction "VDDA1P3_TX_VCO_LDO_B10") (pintype "passive"))
      (node (ref "U5") (pin "B9") (pinfunction "VDDA1P3_TX_LO_B9") (pintype "passive"))
      (node (ref "U5") (pin "E2") (pinfunction "VDDA1P3_RX_LO_E2") (pintype "passive"))
      (node (ref "U5") (pin "F2") (pinfunction "VDDA1P3_RX_VCO_LDO_F2") (pintype "passive"))
      (node (ref "U5") (pin "J3") (pinfunction "VDDA1P3_RX_SYNTH_J3") (pintype "passive"))
      (node (ref "U5") (pin "K3") (pinfunction "VDDA1P3_TX_SYNTH_K3") (pintype "passive"))
    )
    (net (code "83") (name "VCC1P8") (class "Default")
      (node (ref "C143") (pin "2") (pinfunction "2_2") (pintype "passive"))
      (node (ref "C144") (pin "2") (pinfunction "2_2") (pintype "passive"))
      (node (ref "CP2") (pin "1") (pinfunction "1_1") (pintype "passive"))
      (node (ref "CP3") (pin "2") (pinfunction "2_2") (pintype "passive"))
      (node (ref "LP1") (pin "2") (pinfunction "2_2") (pintype "passive"))
      (node (ref "RP2") (pin "1") (pinfunction "1_1") (pintype "passive"))
      (node (ref "U5") (pin "H12") (pinfunction "VDD_INTERFACE_H12") (pintype "passive"))
      (node (ref "X4") (pin "4") (pinfunction "VCC_4") (pintype "power_in"))
    )
    (net (code "84") (name "VCC_3V3") (class "Default")
      (node (ref "CP1") (pin "2") (pinfunction "2_2") (pintype "passive"))
      (node (ref "UP1") (pin "1") (pinfunction "EN_1") (pintype "passive"))
      (node (ref "UP1") (pin "4") (pinfunction "VIN_4") (pintype "passive"))
    )
    (net (code "85") (name "unconnected-(U5A-AUXADC-PadL5)") (class "Default")
      (node (ref "U5") (pin "L5") (pinfunction "AUXADC_L5") (pintype "passive+no_connect"))
    )
    (net (code "86") (name "unconnected-(U5A-AUXDAC1-PadB3)") (class "Default")
      (node (ref "U5") (pin "B3") (pinfunction "AUXDAC1_B3") (pintype "passive+no_connect"))
    )
    (net (code "87") (name "unconnected-(U5A-AUXDAC2-PadC3)") (class "Default")
      (node (ref "U5") (pin "C3") (pinfunction "AUXDAC2_C3") (pintype "passive+no_connect"))
    )
    (net (code "88") (name "unconnected-(U5B-DNC-PadA3)") (class "Default")
      (node (ref "U5") (pin "A3") (pinfunction "DNC_A3") (pintype "passive+no_connect"))
    )
    (net (code "89") (name "unconnected-(U5B-DNC-PadM3)") (class "Default")
      (node (ref "U5") (pin "M3") (pinfunction "DNC_M3") (pintype "passive+no_connect"))
    )
    (net (code "90") (name "unconnected-(U5B-DNC-PadM11)") (class "Default")
      (node (ref "U5") (pin "M11") (pinfunction "DNC_M11") (pintype "passive+no_connect"))
    )
    (net (code "91") (name "unconnected-(U5C-GPO_0-PadB7)") (class "Default")
      (node (ref "U5") (pin "B7") (pinfunction "GPO_0_B7") (pintype "passive+no_connect"))
    )
    (net (code "92") (name "unconnected-(U5C-GPO_1-PadB6)") (class "Default")
      (node (ref "U5") (pin "B6") (pinfunction "GPO_1_B6") (pintype "passive+no_connect"))
    )
    (net (code "93") (name "unconnected-(U5C-GPO_2-PadB5)") (class "Default")
      (node (ref "U5") (pin "B5") (pinfunction "GPO_2_B5") (pintype "passive+no_connect"))
    )
    (net (code "94") (name "unconnected-(U5C-GPO_3-PadB4)") (class "Default")
      (node (ref "U5") (pin "B4") (pinfunction "GPO_3_B4") (pintype "passive+no_connect"))
    )
    (net (code "95") (name "unconnected-(UP1-NC-Pad5)") (class "Default")
      (node (ref "UP1") (pin "5") (pinfunction "NC_5") (pintype "passive"))
    )
    (net (code "96") (name "unconnected-(X4-NC-Pad1)") (class "Default")
      (node (ref "X4") (pin "1") (pinfunction "NC_1") (pintype "passive"))
    )
  )
)
